# ovl_dac_panel.net
KiCad netlist of a schematic drawn in EAGLE
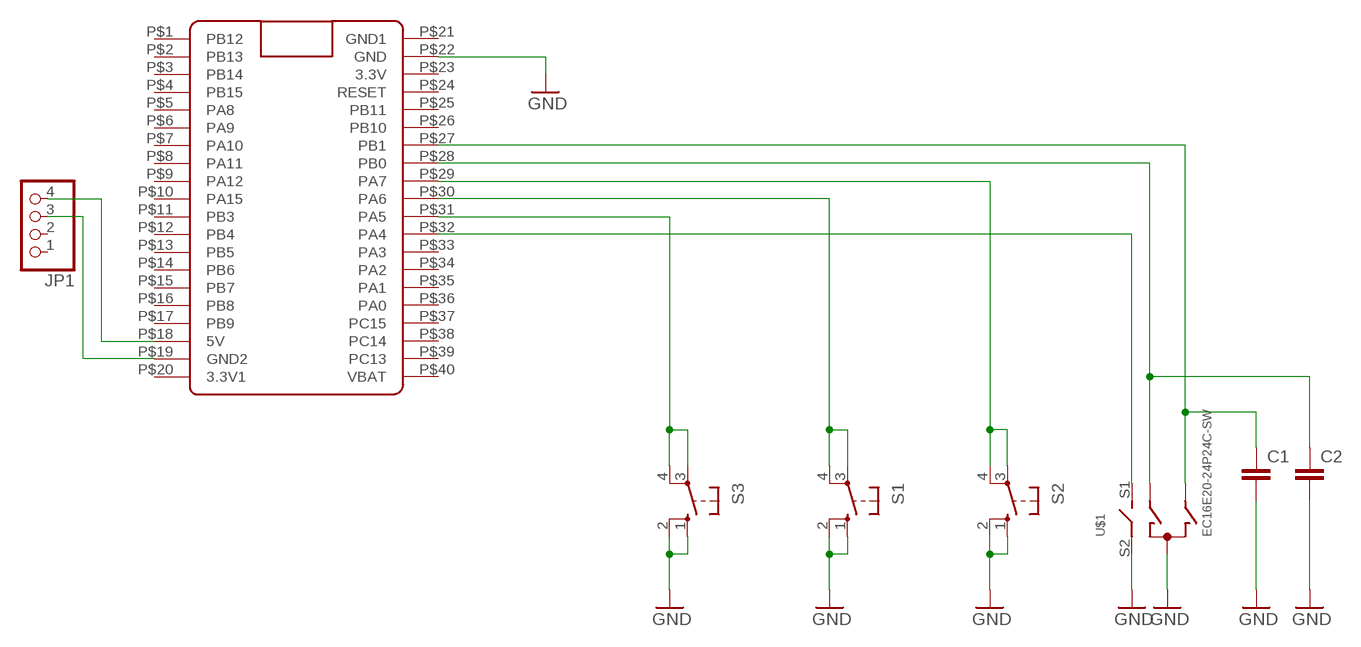
[diagram p0: schematic, sheet 1]

(export (version "E")
  (design (tool "Eeschema 10.0.6"))
  (components
    (comp (ref "C1")
      (value "C-EUC0805")
      (footprint "eagle-import:C0805")
      (libsource (lib "eagle-import") (part "C-EUC0805"))
    )
    (comp (ref "C2")
      (value "C-EUC0805")
      (footprint "eagle-import:C0805")
      (libsource (lib "eagle-import") (part "C-EUC0805"))
    )
    (comp (ref "JP1")
      (value "PINHD-1X4")
      (footprint "eagle-import:1X04")
      (libsource (lib "eagle-import") (part "PINHD-1X4"))
    )
    (comp (ref "S1")
      (value "10-XX")
      (footprint "eagle-import:B3F-10XX")
      (fields (field (name "MPN") "B3F-1000"))
      (libsource (lib "eagle-import") (part "10-XX"))
    )
    (comp (ref "S2")
      (value "10-XX")
      (footprint "eagle-import:B3F-10XX")
      (fields (field (name "MPN") "B3F-1000"))
      (libsource (lib "eagle-import") (part "10-XX"))
    )
    (comp (ref "S3")
      (value "10-XX")
      (footprint "eagle-import:B3F-10XX")
      (fields (field (name "MPN") "B3F-1000"))
      (libsource (lib "eagle-import") (part "10-XX"))
    )
    (comp (ref "U$1")
      (value "EC16E20-24P24C-SW")
      (footprint "eagle-import:EC16E20-24P24C-SW")
      (libsource (lib "eagle-import") (part "EC16E20-24P24C-SW"))
    )
    (comp (ref "U$2")
      (value "BLUE_PILL")
      (footprint "eagle-import:BLUE_PILL")
      (libsource (lib "eagle-import") (part "BLUE_PILL"))
    )
  )
  (nets
    (net (code "1") (name "/GND1") (class "Default")
      (node (ref "U$2") (pin "P$21") (pinfunction "GND1_P$21") (pintype "power_in"))
    )
    (net (code "2") (name "GND") (class "Default")
      (node (ref "C1") (pin "2") (pinfunction "2_2") (pintype "passive"))
      (node (ref "C2") (pin "2") (pinfunction "2_2") (pintype "passive"))
      (node (ref "S1") (pin "1") (pinfunction "S_1") (pintype "passive"))
      (node (ref "S1") (pin "2") (pinfunction "S1_2") (pintype "passive"))
      (node (ref "S2") (pin "1") (pinfunction "S_1") (pintype "passive"))
      (node (ref "S2") (pin "2") (pinfunction "S1_2") (pintype "passive"))
      (node (ref "S3") (pin "1") (pinfunction "S_1") (pintype "passive"))
      (node (ref "S3") (pin "2") (pinfunction "S1_2") (pintype "passive"))
      (node (ref "U$1") (pin "C") (pinfunction "C_C") (pintype "passive"))
      (node (ref "U$1") (pin "S2") (pinfunction "S2_S2") (pintype "bidirectional"))
      (node (ref "U$2") (pin "P$22") (pinfunction "GND_P$22") (pintype "bidirectional"))
    )
    (net (code "3") (name "Net-(S1-P)") (class "Default")
      (node (ref "S1") (pin "3") (pinfunction "P_3") (pintype "passive"))
      (node (ref "S1") (pin "4") (pinfunction "P1_4") (pintype "passive"))
      (node (ref "U$2") (pin "P$30") (pinfunction "PA6_P$30") (pintype "bidirectional"))
    )
    (net (code "4") (name "Net-(S2-P)") (class "Default")
      (node (ref "S2") (pin "3") (pinfunction "P_3") (pintype "passive"))
      (node (ref "S2") (pin "4") (pinfunction "P1_4") (pintype "passive"))
      (node (ref "U$2") (pin "P$29") (pinfunction "PA7_P$29") (pintype "bidirectional"))
    )
    (net (code "5") (name "Net-(S3-P)") (class "Default")
      (node (ref "S3") (pin "3") (pinfunction "P_3") (pintype "passive"))
      (node (ref "S3") (pin "4") (pinfunction "P1_4") (pintype "passive"))
      (node (ref "U$2") (pin "P$31") (pinfunction "PA5_P$31") (pintype "bidirectional"))
    )
    (net (code "6") (name "Net-(U$2-5V)") (class "Default")
      (node (ref "JP1") (pin "4") (pinfunction "4_4") (pintype "passive"))
      (node (ref "U$2") (pin "P$18") (pinfunction "5V_P$18") (pintype "bidirectional"))
    )
    (net (code "7") (name "Net-(U$2-GND2)") (class "Default")
      (node (ref "JP1") (pin "3") (pinfunction "3_3") (pintype "passive"))
      (node (ref "U$2") (pin "P$19") (pinfunction "GND2_P$19") (pintype "bidirectional"))
    )
    (net (code "8") (name "Net-(U$2-PA4)") (class "Default")
      (node (ref "U$1") (pin "S1") (pinfunction "S1_S1") (pintype "bidirectional"))
      (node (ref "U$2") (pin "P$32") (pinfunction "PA4_P$32") (pintype "bidirectional"))
    )
    (net (code "9") (name "Net-(U$2-PB0)") (class "Default")
      (node (ref "C2") (pin "1") (pinfunction "1_1") (pintype "passive"))
      (node (ref "U$1") (pin "A") (pinfunction "A_A") (pintype "passive"))
      (node (ref "U$2") (pin "P$28") (pinfunction "PB0_P$28") (pintype "bidirectional"))
    )
    (net (code "10") (name "Net-(U$2-PB1)") (class "Default")
      (node (ref "C1") (pin "1") (pinfunction "1_1") (pintype "passive"))
      (node (ref "U$1") (pin "B") (pinfunction "B_B") (pintype "passive"))
      (node (ref "U$2") (pin "P$27") (pinfunction "PB1_P$27") (pintype "bidirectional"))
    )
    (net (code "11") (name "unconnected-(JP1-Pad1)") (class "Default")
      (node (ref "JP1") (pin "1") (pinfunction "1_1") (pintype "passive"))
    )
    (net (code "12") (name "unconnected-(JP1-Pad2)") (class "Default")
      (node (ref "JP1") (pin "2") (pinfunction "2_2") (pintype "passive"))
    )
    (net (code "13") (name "unconnected-(U$2-3.3V-PadP$23)") (class "Default")
      (node (ref "U$2") (pin "P$23") (pinfunction "3.3V_P$23") (pintype "bidirectional"))
    )
    (net (code "14") (name "unconnected-(U$2-3.3V1-PadP$20)") (class "Default")
      (node (ref "U$2") (pin "P$20") (pinfunction "3.3V1_P$20") (pintype "bidirectional"))
    )
    (net (code "15") (name "unconnected-(U$2-PA0-PadP$36)") (class "Default")
      (node (ref "U$2") (pin "P$36") (pinfunction "PA0_P$36") (pintype "bidirectional"))
    )
    (net (code "16") (name "unconnected-(U$2-PA1-PadP$35)") (class "Default")
      (node (ref "U$2") (pin "P$35") (pinfunction "PA1_P$35") (pintype "bidirectional"))
    )
    (net (code "17") (name "unconnected-(U$2-PA2-PadP$34)") (class "Default")
      (node (ref "U$2") (pin "P$34") (pinfunction "PA2_P$34") (pintype "bidirectional"))
    )
    (net (code "18") (name "unconnected-(U$2-PA3-PadP$33)") (class "Default")
      (node (ref "U$2") (pin "P$33") (pinfunction "PA3_P$33") (pintype "bidirectional"))
    )
    (net (code "19") (name "unconnected-(U$2-PA8-PadP$5)") (class "Default")
      (node (ref "U$2") (pin "P$5") (pinfunction "PA8_P$5") (pintype "bidirectional"))
    )
    (net (code "20") (name "unconnected-(U$2-PA9-PadP$6)") (class "Default")
      (node (ref "U$2") (pin "P$6") (pinfunction "PA9_P$6") (pintype "bidirectional"))
    )
    (net (code "21") (name "unconnected-(U$2-PA10-PadP$7)") (class "Default")
      (node (ref "U$2") (pin "P$7") (pinfunction "PA10_P$7") (pintype "bidirectional"))
    )
    (net (code "22") (name "unconnected-(U$2-PA11-PadP$8)") (class "Default")
      (node (ref "U$2") (pin "P$8") (pinfunction "PA11_P$8") (pintype "bidirectional"))
    )
    (net (code "23") (name "unconnected-(U$2-PA12-PadP$9)") (class "Default")
      (node (ref "U$2") (pin "P$9") (pinfunction "PA12_P$9") (pintype "bidirectional"))
    )
    (net (code "24") (name "unconnected-(U$2-PA15-PadP$10)") (class "Default")
      (node (ref "U$2") (pin "P$10") (pinfunction "PA15_P$10") (pintype "bidirectional"))
    )
    (net (code "25") (name "unconnected-(U$2-PB3-PadP$11)") (class "Default")
      (node (ref "U$2") (pin "P$11") (pinfunction "PB3_P$11") (pintype "bidirectional"))
    )
    (net (code "26") (name "unconnected-(U$2-PB4-PadP$12)") (class "Default")
      (node (ref "U$2") (pin "P$12") (pinfunction "PB4_P$12") (pintype "bidirectional"))
    )
    (net (code "27") (name "unconnected-(U$2-PB5-PadP$13)") (class "Default")
      (node (ref "U$2") (pin "P$13") (pinfunction "PB5_P$13") (pintype "bidirectional"))
    )
    (net (code "28") (name "unconnected-(U$2-PB6-PadP$14)") (class "Default")
      (node (ref "U$2") (pin "P$14") (pinfunction "PB6_P$14") (pintype "bidirectional"))
    )
    (net (code "29") (name "unconnected-(U$2-PB7-PadP$15)") (class "Default")
      (node (ref "U$2") (pin "P$15") (pinfunction "PB7_P$15") (pintype "bidirectional"))
    )
    (net (code "30") (name "unconnected-(U$2-PB8-PadP$16)") (class "Default")
      (node (ref "U$2") (pin "P$16") (pinfunction "PB8_P$16") (pintype "bidirectional"))
    )
    (net (code "31") (name "unconnected-(U$2-PB9-PadP$17)") (class "Default")
      (node (ref "U$2") (pin "P$17") (pinfunction "PB9_P$17") (pintype "bidirectional"))
    )
    (net (code "32") (name "unconnected-(U$2-PB10-PadP$26)") (class "Default")
      (node (ref "U$2") (pin "P$26") (pinfunction "PB10_P$26") (pintype "bidirectional"))
    )
    (net (code "33") (name "unconnected-(U$2-PB11-PadP$25)") (class "Default")
      (node (ref "U$2") (pin "P$25") (pinfunction "PB11_P$25") (pintype "bidirectional"))
    )
    (net (code "34") (name "unconnected-(U$2-PB12-PadP$1)") (class "Default")
      (node (ref "U$2") (pin "P$1") (pinfunction "PB12_P$1") (pintype "bidirectional"))
    )
    (net (code "35") (name "unconnected-(U$2-PB13-PadP$2)") (class "Default")
      (node (ref "U$2") (pin "P$2") (pinfunction "PB13_P$2") (pintype "bidirectional"))
    )
    (net (code "36") (name "unconnected-(U$2-PB14-PadP$3)") (class "Default")
      (node (ref "U$2") (pin "P$3") (pinfunction "PB14_P$3") (pintype "bidirectional"))
    )
    (net (code "37") (name "unconnected-(U$2-PB15-PadP$4)") (class "Default")
      (node (ref "U$2") (pin "P$4") (pinfunction "PB15_P$4") (pintype "bidirectional"))
    )
    (net (code "38") (name "unconnected-(U$2-PC13-PadP$39)") (class "Default")
      (node (ref "U$2") (pin "P$39") (pinfunction "PC13_P$39") (pintype "bidirectional"))
    )
    (net (code "39") (name "unconnected-(U$2-PC14-PadP$38)") (class "Default")
      (node (ref "U$2") (pin "P$38") (pinfunction "PC14_P$38") (pintype "bidirectional"))
    )
    (net (code "40") (name "unconnected-(U$2-PC15-PadP$37)") (class "Default")
      (node (ref "U$2") (pin "P$37") (pinfunction "PC15_P$37") (pintype "bidirectional"))
    )
    (net (code "41") (name "unconnected-(U$2-RESET-PadP$24)") (class "Default")
      (node (ref "U$2") (pin "P$24") (pinfunction "RESET_P$24") (pintype "bidirectional"))
    )
    (net (code "42") (name "unconnected-(U$2-VBAT-PadP$40)") (class "Default")
      (node (ref "U$2") (pin "P$40") (pinfunction "VBAT_P$40") (pintype "bidirectional"))
    )
  )
)
